# DigitalInput.net
KiCad netlist of a schematic drawn in Altium Designer
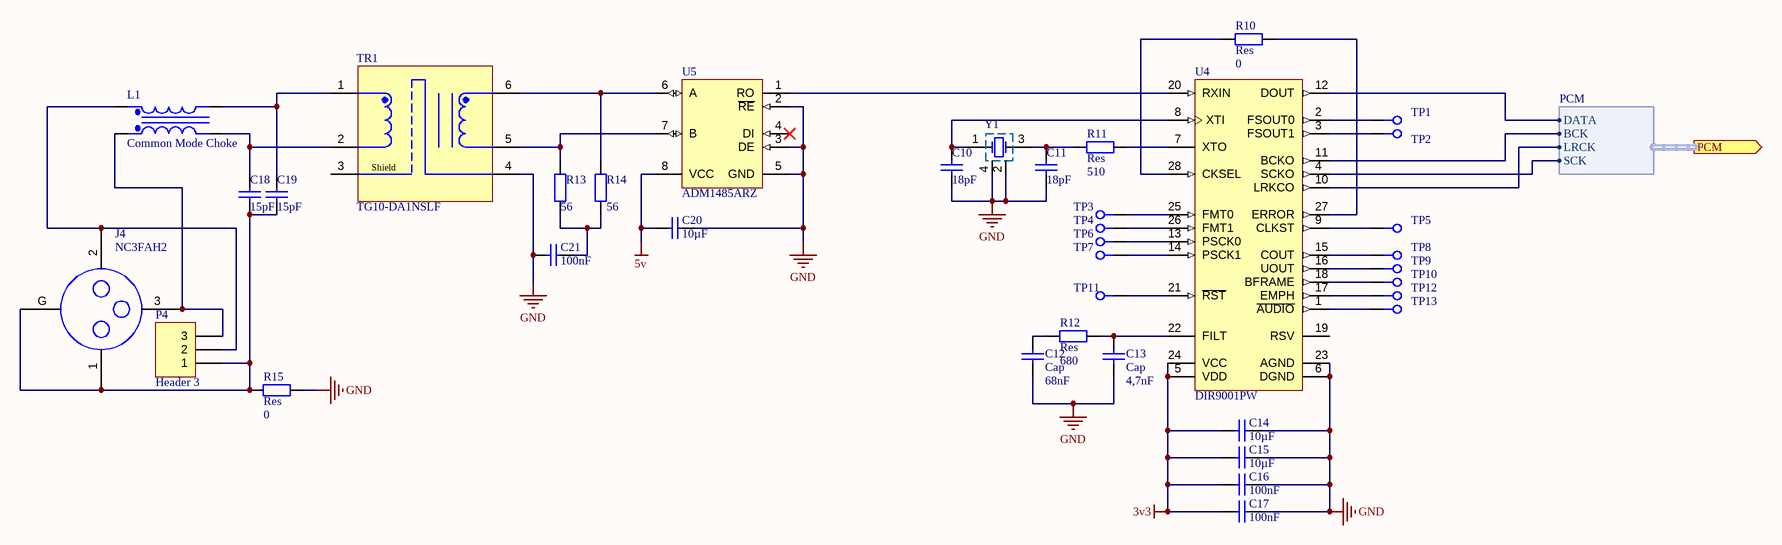
[diagram p0: DigitalInput.SchDoc]

(export (version "E")
  (design (tool "Eeschema 10.0.6"))
  (components
    (comp (ref "C10")
      (value "18pF")
      (footprint "CAPC1005X56X25NL10T15")
      (description "Chip cap 18p 50V - 0402")
      (fields (field (name "TOLERANCE") "5%") (field (name "ZENITEL PARTNUMBER") "4000080916"))
      (libsource (lib "Zenitel Concord PRO Vault") (part "Capacitor-IEC"))
    )
    (comp (ref "C11")
      (value "18pF")
      (footprint "CAPC1005X56X25NL10T15")
      (description "Chip cap 18p 50V - 0402")
      (fields (field (name "TOLERANCE") "5%") (field (name "ZENITEL PARTNUMBER") "4000080916"))
      (libsource (lib "Zenitel Concord PRO Vault") (part "Capacitor-IEC"))
    )
    (comp (ref "C12")
      (value "Cap")
      (footprint "CAPC1005X56X25ML10T15")
      (description "Chip cap 68n 10V - 0402")
      (fields
        (field (name "ALTIUM_VALUE") "68nF")
        (field (name "VOLTAGE") "10V")
        (field (name "TOLERANCE") "100%")
      )
      (libsource (lib "Zenitel Concord PRO Vault") (part "Capacitor-IEC"))
    )
    (comp (ref "C13")
      (value "Cap")
      (footprint "CAPC1005X56X25LL10T15")
      (description "Chip cap 4700p 50V - 0402")
      (fields
        (field (name "ALTIUM_VALUE") "4,7nF")
        (field (name "ZENITEL PARTNUMBER") "4000080940")
        (field (name "VOLTAGE") "50V")
      )
      (libsource (lib "Zenitel Concord PRO Vault") (part "Capacitor-IEC"))
    )
    (comp (ref "C14")
      (value "10µF")
      (footprint "CAPC2013X140X50LL20T25")
      (description "CR0805 10u 10V X7R 10% h=1.25mm")
      (fields (field (name "TOLERANCE") "10%") (field (name "VOLTAGE") "10V"))
      (libsource (lib "Zenitel Concord PRO Vault") (part "Capacitor-IEC"))
    )
    (comp (ref "C15")
      (value "10µF")
      (footprint "CAPC2013X140X50LL20T25")
      (description "CR0805 10u 10V X7R 10% h=1.25mm")
      (fields (field (name "TOLERANCE") "10%") (field (name "VOLTAGE") "10V"))
      (libsource (lib "Zenitel Concord PRO Vault") (part "Capacitor-IEC"))
    )
    (comp (ref "C16")
      (value "100nF")
      (footprint "CAPC1005X56X25NL10T15")
      (description "Chip cap  100n 10V - 0402  X7R")
      (fields (field (name "TOLERANCE") "10%") (field (name "VOLTAGE") "10V"))
      (libsource (lib "Zenitel Concord PRO Vault") (part "Capacitor-IEC"))
    )
    (comp (ref "C17")
      (value "100nF")
      (footprint "CAPC1005X56X25NL10T15")
      (description "Chip cap  100n 10V - 0402  X7R")
      (fields (field (name "TOLERANCE") "10%") (field (name "VOLTAGE") "10V"))
      (libsource (lib "Zenitel Concord PRO Vault") (part "Capacitor-IEC"))
    )
    (comp (ref "C18")
      (value "15pF")
      (footprint "CAPC1005X56X25NL10T15")
      (description "Chip cap 15pF 50V NP0 - 0402")
      (fields (field (name "TOLERANCE") "1%") (field (name "ZENITEL PARTNUMBER") "EFSMD17120"))
      (libsource (lib "Zenitel Concord PRO Vault") (part "Capacitor-IEC"))
    )
    (comp (ref "C19")
      (value "15pF")
      (footprint "CAPC1005X56X25NL10T15")
      (description "Chip cap 15pF 50V NP0 - 0402")
      (fields (field (name "TOLERANCE") "1%") (field (name "ZENITEL PARTNUMBER") "EFSMD17120"))
      (libsource (lib "Zenitel Concord PRO Vault") (part "Capacitor-IEC"))
    )
    (comp (ref "C20")
      (value "10µF")
      (footprint "CAPC2013X140X50LL20T25")
      (description "CR0805 10u 10V X7R 10% h=1.25mm")
      (fields (field (name "TOLERANCE") "10%") (field (name "VOLTAGE") "10V"))
      (libsource (lib "Zenitel Concord PRO Vault") (part "Capacitor-IEC"))
    )
    (comp (ref "C21")
      (value "100nF")
      (footprint "CAPC1608X90X35ML15T15")
      (description "Chip cap  100n 50V X7R - 0603")
      (fields (field (name "ZENITEL PARTNUMBER") "4000084734") (field (name "TOLERANCE") "10%"))
      (libsource (lib "Zenitel Concord PRO Vault") (part "Capacitor-IEC"))
    )
    (comp (ref "J4")
      (value "NC3FAH2")
      (footprint "NC3FAH2")
      (description "NC3FAH2 3pole female XLR 90deg")
      (fields (field (name "ZENITEL PARTNUMBER") "4000083398"))
      (libsource (lib "Zenitel Concord PRO Vault") (part "NC3FAH2"))
    )
    (comp (ref "L1")
      (value "Common Mode Choke")
      (footprint "WE-CNSW-1206")
      (description "WE-CNSW SMD Common Mode Line Filter")
      (fields (field (name "ZENITEL PARTNUMBER") "4000086128"))
      (libsource (lib "Zenitel Concord PRO Vault") (part "Common Mode Choke"))
    )
    (comp (ref "P4")
      (value "Header 3")
      (footprint "MTA-100-3P")
      (description "MTA-100-3P 3-pin header")
      (fields (field (name "ZENITEL PARTNUMBER") "4000085467"))
      (libsource (lib "Zenitel Concord PRO Vault") (part "Header 3"))
    )
    (comp (ref "R10")
      (value "Res")
      (footprint "RESC1005X40X25NL05T05")
      (description "Chip resistor 0R - 0402")
      (fields
        (field (name "ALTIUM_VALUE") "0")
        (field (name "POWER") "62,5mW")
        (field (name "TOLERANCE") "1%")
      )
      (libsource (lib "") (part "Resistor-IEC_2"))
    )
    (comp (ref "R11")
      (value "Res")
      (footprint "RESC1005X40X25NL05T05")
      (description "Chip resistor 0402 - 510R 1%")
      (fields
        (field (name "ALTIUM_VALUE") "510")
        (field (name "TOLERANCE") "1%")
        (field (name "ZENITEL PARTNUMBER") "4000088250")
      )
      (libsource (lib "") (part "Resistor-IEC_2"))
    )
    (comp (ref "R12")
      (value "Res")
      (footprint "RESC1005X40X25NL05T05")
      (description "Chip resistor 680R - 0402")
      (fields
        (field (name "ALTIUM_VALUE") "680")
        (field (name "POWER") "62,5mW")
        (field (name "TOLERANCE") "1%")
      )
      (libsource (lib "") (part "Resistor-IEC_2"))
    )
    (comp (ref "R13")
      (value "56")
      (footprint "RESC1609X50X30ML10T20")
      (description "CR 0603 56R 5%")
      (fields (field (name "ZENITEL PARTNUMBER") "4000098393") (field (name "POWER") "100mW"))
      (libsource (lib "Zenitel Concord PRO Vault") (part "Resistor-IEC"))
    )
    (comp (ref "R14")
      (value "56")
      (footprint "RESC1609X50X30ML10T20")
      (description "CR 0603 56R 5%")
      (fields (field (name "ZENITEL PARTNUMBER") "4000098393") (field (name "POWER") "100mW"))
      (libsource (lib "Zenitel Concord PRO Vault") (part "Resistor-IEC"))
    )
    (comp (ref "R15")
      (value "Res")
      (footprint "RESC3216X60X45LL10T20")
      (description "0R 1206")
      (fields
        (field (name "ALTIUM_VALUE") "0")
        (field (name "ZENITEL PARTNUMBER") "4000085059")
        (field (name "POWER") "250mW")
      )
      (libsource (lib "") (part "Resistor-IEC_1"))
    )
    (comp (ref "TP1")
      (value "TP Ø1.27MM")
      (footprint "TP_1.27MM")
      (description "Test Point, copper pad, 1.27mm diameter")
      (libsource (lib "Zenitel Concord PRO Vault") (part "Symbol"))
    )
    (comp (ref "TP2")
      (value "TP Ø1.27MM")
      (footprint "TP_1.27MM")
      (description "Test Point, copper pad, 1.27mm diameter")
      (libsource (lib "Zenitel Concord PRO Vault") (part "Symbol"))
    )
    (comp (ref "TP3")
      (value "TP Ø1.27MM")
      (footprint "TP_1.27MM")
      (description "Test Point, copper pad, 1.27mm diameter")
      (libsource (lib "Zenitel Concord PRO Vault") (part "Symbol"))
    )
    (comp (ref "TP4")
      (value "TP Ø1.27MM")
      (footprint "TP_1.27MM")
      (description "Test Point, copper pad, 1.27mm diameter")
      (libsource (lib "Zenitel Concord PRO Vault") (part "Symbol"))
    )
    (comp (ref "TP5")
      (value "TP Ø1.27MM")
      (footprint "TP_1.27MM")
      (description "Test Point, copper pad, 1.27mm diameter")
      (libsource (lib "Zenitel Concord PRO Vault") (part "Symbol"))
    )
    (comp (ref "TP6")
      (value "TP Ø1.27MM")
      (footprint "TP_1.27MM")
      (description "Test Point, copper pad, 1.27mm diameter")
      (libsource (lib "Zenitel Concord PRO Vault") (part "Symbol"))
    )
    (comp (ref "TP7")
      (value "TP Ø1.27MM")
      (footprint "TP_1.27MM")
      (description "Test Point, copper pad, 1.27mm diameter")
      (libsource (lib "Zenitel Concord PRO Vault") (part "Symbol"))
    )
    (comp (ref "TP8")
      (value "TP Ø1.27MM")
      (footprint "TP_1.27MM")
      (description "Test Point, copper pad, 1.27mm diameter")
      (libsource (lib "Zenitel Concord PRO Vault") (part "Symbol"))
    )
    (comp (ref "TP9")
      (value "TP Ø1.27MM")
      (footprint "TP_1.27MM")
      (description "Test Point, copper pad, 1.27mm diameter")
      (libsource (lib "Zenitel Concord PRO Vault") (part "Symbol"))
    )
    (comp (ref "TP10")
      (value "TP Ø1.27MM")
      (footprint "TP_1.27MM")
      (description "Test Point, copper pad, 1.27mm diameter")
      (libsource (lib "Zenitel Concord PRO Vault") (part "Symbol"))
    )
    (comp (ref "TP11")
      (value "TP Ø1.27MM")
      (footprint "TP_1.27MM")
      (description "Test Point, copper pad, 1.27mm diameter")
      (libsource (lib "Zenitel Concord PRO Vault") (part "Symbol"))
    )
    (comp (ref "TP12")
      (value "TP Ø1.27MM")
      (footprint "TP_1.27MM")
      (description "Test Point, copper pad, 1.27mm diameter")
      (libsource (lib "Zenitel Concord PRO Vault") (part "Symbol"))
    )
    (comp (ref "TP13")
      (value "TP Ø1.27MM")
      (footprint "TP_1.27MM")
      (description "Test Point, copper pad, 1.27mm diameter")
      (libsource (lib "Zenitel Concord PRO Vault") (part "Symbol"))
    )
    (comp (ref "TR1")
      (value "TG10-DA1NSLF")
      (footprint "TG10-DA1NSLF-Footprint-1")
      (description "Audio Transformers / Signal Transformers ISO MOD GullWng Sgl Audio w/ shield 6pin")
      (libsource (lib "Zenitel Concord PRO Vault") (part "TG10-DA1NSLF"))
    )
    (comp (ref "U4")
      (value "DIR9001PW")
      (footprint "PW0028A_N")
      (fields (field (name "MANUFACTURER") "Texas Instruments"))
      (libsource (lib "Altium Content Vault") (part "TI-DIR9001-TSSOP_PW-28"))
    )
    (comp (ref "U5")
      (value "ADM1485ARZ")
      (footprint "ADI-R-8_M")
      (fields (field (name "MANUFACTURER") "Analog Devices"))
      (libsource (lib "Altium Content Vault") (part "ADI-ADM3483_5-R-8"))
    )
    (comp (ref "Y1")
      (value "Crystal4")
      (footprint "XTAL-5x3.2MM")
      (description "Crystal 24.576MHZ 18pF 5X3.2mm")
      (fields (field (name "ZENITEL PARTNUMBER") "4000086516"))
      (libsource (lib "Zenitel Concord PRO Vault") (part "Crystal4"))
    )
  )
  (nets
    (net (code "2") (name "/BCK") (class "Default")
      (node (ref "U4") (pin "11") (pinfunction "BCKO_11") (pintype "output"))
    )
    (net (code "3") (name "/DATA") (class "Default")
      (node (ref "U4") (pin "12") (pinfunction "DOUT_12") (pintype "output"))
    )
    (net (code "4") (name "/LRCK") (class "Default")
      (node (ref "U4") (pin "10") (pinfunction "LRKCO_10") (pintype "output"))
    )
    (net (code "5") (name "/SCK") (class "Default")
      (node (ref "U4") (pin "4") (pinfunction "SCKO_4") (pintype "output"))
    )
    (net (code "7") (name "3v3") (class "Default")
      (node (ref "C14") (pin "2") (pinfunction "2_2") (pintype "passive"))
      (node (ref "C15") (pin "2") (pinfunction "2_2") (pintype "passive"))
      (node (ref "C16") (pin "1") (pinfunction "1_1") (pintype "passive"))
      (node (ref "C17") (pin "1") (pinfunction "1_1") (pintype "passive"))
      (node (ref "U4") (pin "24") (pinfunction "VCC_24") (pintype "power_in"))
      (node (ref "U4") (pin "5") (pinfunction "VDD_5") (pintype "power_in"))
    )
    (net (code "8") (name "5v") (class "Default")
      (node (ref "C20") (pin "2") (pinfunction "2_2") (pintype "passive"))
      (node (ref "U5") (pin "8") (pinfunction "VCC_8") (pintype "power_in"))
    )
    (net (code "9") (name "GND") (class "Default")
      (node (ref "C10") (pin "1") (pinfunction "1_1") (pintype "passive"))
      (node (ref "C11") (pin "1") (pinfunction "1_1") (pintype "passive"))
      (node (ref "C12") (pin "1") (pinfunction "1_1") (pintype "passive"))
      (node (ref "C13") (pin "1") (pinfunction "1_1") (pintype "passive"))
      (node (ref "C14") (pin "1") (pinfunction "1_1") (pintype "passive"))
      (node (ref "C15") (pin "1") (pinfunction "1_1") (pintype "passive"))
      (node (ref "C16") (pin "2") (pinfunction "2_2") (pintype "passive"))
      (node (ref "C17") (pin "2") (pinfunction "2_2") (pintype "passive"))
      (node (ref "C20") (pin "1") (pinfunction "1_1") (pintype "passive"))
      (node (ref "C21") (pin "1") (pinfunction "1_1") (pintype "passive"))
      (node (ref "R15") (pin "1") (pinfunction "1_1") (pintype "passive"))
      (node (ref "TR1") (pin "4") (pinfunction "4_4") (pintype "passive"))
      (node (ref "U4") (pin "23") (pinfunction "AGND_23") (pintype "power_in"))
      (node (ref "U4") (pin "6") (pinfunction "DGND_6") (pintype "power_in"))
      (node (ref "U5") (pin "2") (pinfunction "~{RE}_2") (pintype "input"))
      (node (ref "U5") (pin "3") (pinfunction "DE_3") (pintype "input"))
      (node (ref "U5") (pin "5") (pinfunction "GND_5") (pintype "power_in"))
      (node (ref "Y1") (pin "2") (pinfunction "GND_2") (pintype "power_in"))
      (node (ref "Y1") (pin "4") (pinfunction "4_4") (pintype "passive"))
    )
    (net (code "10") (name "Net-(C12-Pad2)") (class "Default")
      (node (ref "C12") (pin "2") (pinfunction "2_2") (pintype "passive"))
      (node (ref "R12") (pin "1") (pinfunction "1_1") (pintype "passive"))
    )
    (net (code "11") (name "Net-(C18-Pad1)") (class "Default")
      (node (ref "C18") (pin "1") (pinfunction "1_1") (pintype "passive"))
      (node (ref "C19") (pin "1") (pinfunction "1_1") (pintype "passive"))
      (node (ref "J4") (pin "1") (pinfunction "1_1") (pintype "passive"))
      (node (ref "J4") (pin "G") (pinfunction "G_G") (pintype "passive"))
      (node (ref "P4") (pin "1") (pinfunction "1_1") (pintype "passive"))
      (node (ref "R15") (pin "2") (pinfunction "2_2") (pintype "passive"))
    )
    (net (code "12") (name "Net-(C18-Pad2)") (class "Default")
      (node (ref "C18") (pin "2") (pinfunction "2_2") (pintype "passive"))
      (node (ref "L1") (pin "4") (pinfunction "4_4") (pintype "passive"))
      (node (ref "TR1") (pin "2") (pinfunction "2_2") (pintype "passive"))
    )
    (net (code "13") (name "Net-(C19-Pad2)") (class "Default")
      (node (ref "C19") (pin "2") (pinfunction "2_2") (pintype "passive"))
      (node (ref "L1") (pin "3") (pinfunction "3_3") (pintype "passive"))
      (node (ref "TR1") (pin "1") (pinfunction "1_1") (pintype "passive"))
    )
    (net (code "14") (name "Net-(C21-Pad2)") (class "Default")
      (node (ref "C21") (pin "2") (pinfunction "2_2") (pintype "passive"))
      (node (ref "R13") (pin "1") (pinfunction "1_1") (pintype "passive"))
      (node (ref "R14") (pin "1") (pinfunction "1_1") (pintype "passive"))
    )
    (net (code "15") (name "Net-(J4-Pad2)") (class "Default")
      (node (ref "J4") (pin "2") (pinfunction "2_2") (pintype "passive"))
      (node (ref "L1") (pin "2") (pinfunction "2_2") (pintype "passive"))
      (node (ref "P4") (pin "2") (pinfunction "2_2") (pintype "passive"))
    )
    (net (code "16") (name "Net-(J4-Pad3)") (class "Default")
      (node (ref "J4") (pin "3") (pinfunction "3_3") (pintype "passive"))
      (node (ref "L1") (pin "1") (pinfunction "1_1") (pintype "passive"))
      (node (ref "P4") (pin "3") (pinfunction "3_3") (pintype "passive"))
    )
    (net (code "17") (name "Net-(U4-BFRAME)") (class "Default")
      (node (ref "TP10") (pin "1") (pinfunction "1_1") (pintype "passive"))
      (node (ref "U4") (pin "18") (pinfunction "BFRAME_18") (pintype "output"))
    )
    (net (code "18") (name "Net-(U4-CKSEL)") (class "Default")
      (node (ref "R10") (pin "1") (pinfunction "1_1") (pintype "passive"))
      (node (ref "U4") (pin "28") (pinfunction "CKSEL_28") (pintype "input"))
    )
    (net (code "19") (name "Net-(U4-CLKST)") (class "Default")
      (node (ref "TP5") (pin "1") (pinfunction "1_1") (pintype "passive"))
      (node (ref "U4") (pin "9") (pinfunction "CLKST_9") (pintype "output"))
    )
    (net (code "20") (name "Net-(U4-COUT)") (class "Default")
      (node (ref "TP8") (pin "1") (pinfunction "1_1") (pintype "passive"))
      (node (ref "U4") (pin "15") (pinfunction "COUT_15") (pintype "output"))
    )
    (net (code "21") (name "Net-(U4-EMPH)") (class "Default")
      (node (ref "TP12") (pin "1") (pinfunction "1_1") (pintype "passive"))
      (node (ref "U4") (pin "17") (pinfunction "EMPH_17") (pintype "output"))
    )
    (net (code "22") (name "Net-(U4-ERROR)") (class "Default")
      (node (ref "R10") (pin "2") (pinfunction "2_2") (pintype "passive"))
      (node (ref "U4") (pin "27") (pinfunction "ERROR_27") (pintype "output"))
    )
    (net (code "23") (name "Net-(U4-FILT)") (class "Default")
      (node (ref "C13") (pin "2") (pinfunction "2_2") (pintype "passive"))
      (node (ref "R12") (pin "2") (pinfunction "2_2") (pintype "passive"))
      (node (ref "U4") (pin "22") (pinfunction "FILT_22") (pintype "passive"))
    )
    (net (code "24") (name "Net-(U4-FMT0)") (class "Default")
      (node (ref "TP3") (pin "1") (pinfunction "1_1") (pintype "passive"))
      (node (ref "U4") (pin "25") (pinfunction "FMT0_25") (pintype "input"))
    )
    (net (code "25") (name "Net-(U4-FMT1)") (class "Default")
      (node (ref "TP4") (pin "1") (pinfunction "1_1") (pintype "passive"))
      (node (ref "U4") (pin "26") (pinfunction "FMT1_26") (pintype "input"))
    )
    (net (code "26") (name "Net-(U4-FSOUT0)") (class "Default")
      (node (ref "TP1") (pin "1") (pinfunction "1_1") (pintype "passive"))
      (node (ref "U4") (pin "2") (pinfunction "FSOUT0_2") (pintype "output"))
    )
    (net (code "27") (name "Net-(U4-FSOUT1)") (class "Default")
      (node (ref "TP2") (pin "1") (pinfunction "1_1") (pintype "passive"))
      (node (ref "U4") (pin "3") (pinfunction "FSOUT1_3") (pintype "output"))
    )
    (net (code "28") (name "Net-(U4-PSCK0)") (class "Default")
      (node (ref "TP6") (pin "1") (pinfunction "1_1") (pintype "passive"))
      (node (ref "U4") (pin "13") (pinfunction "PSCK0_13") (pintype "input"))
    )
    (net (code "29") (name "Net-(U4-PSCK1)") (class "Default")
      (node (ref "TP7") (pin "1") (pinfunction "1_1") (pintype "passive"))
      (node (ref "U4") (pin "14") (pinfunction "PSCK1_14") (pintype "input"))
    )
    (net (code "30") (name "Net-(U4-RXIN)") (class "Default")
      (node (ref "U4") (pin "20") (pinfunction "RXIN_20") (pintype "input"))
      (node (ref "U5") (pin "1") (pinfunction "RO_1") (pintype "tri_state"))
    )
    (net (code "31") (name "Net-(U4-UOUT)") (class "Default")
      (node (ref "TP9") (pin "1") (pinfunction "1_1") (pintype "passive"))
      (node (ref "U4") (pin "16") (pinfunction "UOUT_16") (pintype "output"))
    )
    (net (code "32") (name "Net-(U4-XTI)") (class "Default")
      (node (ref "C10") (pin "2") (pinfunction "2_2") (pintype "passive"))
      (node (ref "U4") (pin "8") (pinfunction "XTI_8") (pintype "input"))
      (node (ref "Y1") (pin "1") (pinfunction "OSC1_1") (pintype "passive"))
    )
    (net (code "33") (name "Net-(U4-XTO)") (class "Default")
      (node (ref "R11") (pin "2") (pinfunction "2_2") (pintype "passive"))
      (node (ref "U4") (pin "7") (pinfunction "XTO_7") (pintype "passive"))
    )
    (net (code "34") (name "Net-(U4-~{AUDIO})") (class "Default")
      (node (ref "TP13") (pin "1") (pinfunction "1_1") (pintype "passive"))
      (node (ref "U4") (pin "1") (pinfunction "~{AUDIO}_1") (pintype "output"))
    )
    (net (code "35") (name "Net-(U4-~{RST})") (class "Default")
      (node (ref "TP11") (pin "1") (pinfunction "1_1") (pintype "passive"))
      (node (ref "U4") (pin "21") (pinfunction "~{RST}_21") (pintype "input"))
    )
    (net (code "36") (name "Net-(U5-A)") (class "Default")
      (node (ref "R14") (pin "2") (pinfunction "2_2") (pintype "passive"))
      (node (ref "TR1") (pin "6") (pinfunction "6_6") (pintype "passive"))
      (node (ref "U5") (pin "6") (pinfunction "A_6") (pintype "bidirectional"))
    )
    (net (code "37") (name "Net-(U5-B)") (class "Default")
      (node (ref "R13") (pin "2") (pinfunction "2_2") (pintype "passive"))
      (node (ref "TR1") (pin "5") (pinfunction "5_5") (pintype "passive"))
      (node (ref "U5") (pin "7") (pinfunction "B_7") (pintype "bidirectional"))
    )
    (net (code "38") (name "Net-(Y1-OSC2)") (class "Default")
      (node (ref "C11") (pin "2") (pinfunction "2_2") (pintype "passive"))
      (node (ref "R11") (pin "1") (pinfunction "1_1") (pintype "passive"))
      (node (ref "Y1") (pin "3") (pinfunction "OSC2_3") (pintype "passive"))
    )
    (net (code "39") (name "unconnected-(TR1-Pad3)") (class "Default")
      (node (ref "TR1") (pin "3") (pinfunction "3_3") (pintype "passive"))
    )
    (net (code "40") (name "unconnected-(U4-RSV-Pad19)") (class "Default")
      (node (ref "U4") (pin "19") (pinfunction "RSV_19") (pintype "power_in"))
    )
    (net (code "41") (name "unconnected-(U5-DI-Pad4)") (class "Default")
      (node (ref "U5") (pin "4") (pinfunction "DI_4") (pintype "input+no_connect"))
    )
  )
)
